# power_amplifier.net
KiCad netlist of a schematic drawn in Altium Designer
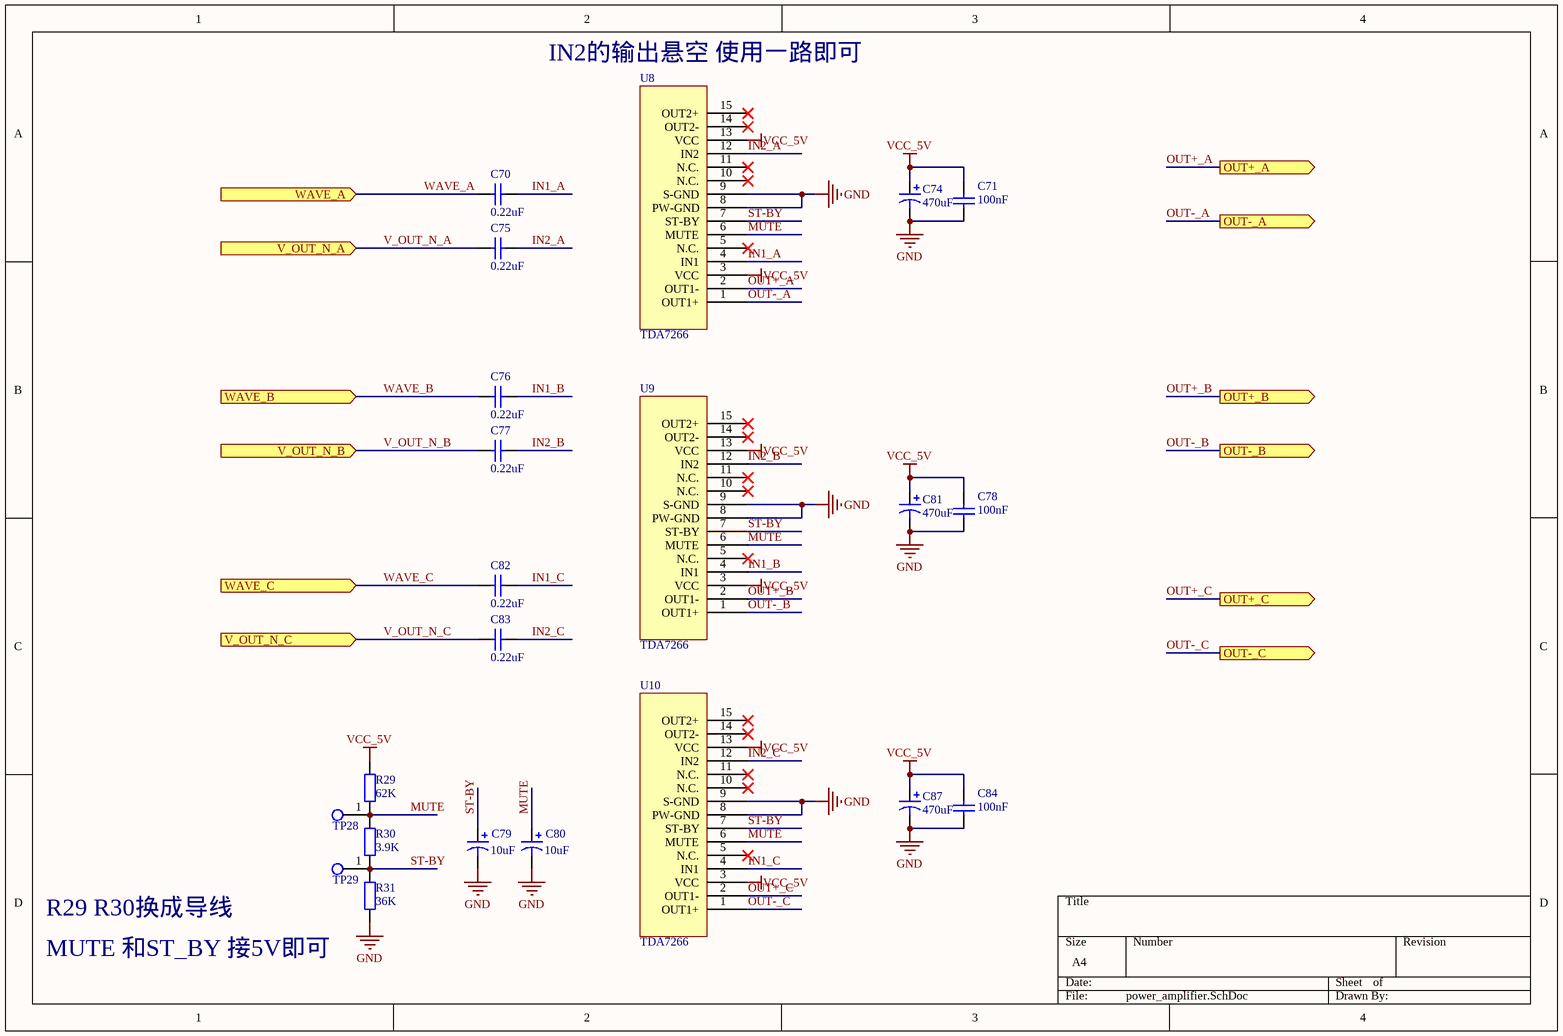
[diagram p0: power_amplifier.SchDoc]

(export (version "E")
  (design (tool "Eeschema 10.0.6"))
  (components
    (comp (ref "C70")
      (value "0.22uF")
      (footprint "0603")
      (fields
        (field (name "Comment") "Cap")
        (field (name "原理图绘制者") "刘永钦")
        (field (name "原理图提供者") "刘永钦")
        (field (name "原理图审核人1") "徐鹏飞")
        (field (name "封装0805绘制者") "刘永钦")
        (field (name "封装0805提供者") "刘永钦")
        (field (name "封装0805审核人1") "徐鹏飞")
        (field (name "原理图审核人2") "朱觉文")
        (field (name "封装0805审核人2") "朱觉文")
        (field (name "封装0603绘制者") "刘永钦")
        (field (name "封装0603提供者") "刘永钦")
        (field (name "封装0603审核人1") "朱觉文")
        (field (name "封装0603审核人2") "徐鹏飞")
      )
      (libsource (lib "自动化研究所集成库20170318") (part "Cap"))
    )
    (comp (ref "C71")
      (value "100nF")
      (footprint "0603")
      (fields
        (field (name "Comment") "Cap")
        (field (name "原理图绘制者") "刘永钦")
        (field (name "原理图提供者") "刘永钦")
        (field (name "原理图审核人1") "徐鹏飞")
        (field (name "封装0805绘制者") "刘永钦")
        (field (name "封装0805提供者") "刘永钦")
        (field (name "封装0805审核人1") "徐鹏飞")
        (field (name "原理图审核人2") "朱觉文")
        (field (name "封装0805审核人2") "朱觉文")
        (field (name "封装0603绘制者") "刘永钦")
        (field (name "封装0603提供者") "刘永钦")
        (field (name "封装0603审核人1") "朱觉文")
        (field (name "封装0603审核人2") "徐鹏飞")
      )
      (libsource (lib "自动化研究所集成库20170318") (part "Cap"))
    )
    (comp (ref "C74")
      (value "470uF")
      (footprint "cap贴片铝电解质470uF 16V")
      (fields
        (field (name "Comment") "Cap Poll")
        (field (name "原理图绘制者") "刘永钦")
        (field (name "原理图提供者") "刘永钦")
        (field (name "原理图审核人1") "徐鹏飞")
        (field (name "封装CAP 钽 7343 E绘制者") "刘永钦")
        (field (name "封装CAP 钽 7343 E提供者") "刘永钦")
        (field (name "封装CAP 钽 7343 E审核人1") "徐鹏飞")
        (field (name "封装CAP贴片铝电解质470UF 16V绘制者") "李泽")
        (field (name "封装CAP贴片铝电解质470UF 16V提供者") "刘永钦")
        (field (name "封装CAP贴片铝电解质470UF 16V审核人1") "徐鹏飞")
        (field (name "封装CAP 3528B绘制者") "陈汉诚")
        (field (name "封装CAP 3528B提供者") "刘永钦")
        (field (name "封装CAP 3528B审核人1") "徐鹏飞")
        (field (name "封装CAP直插 10UF 50V提供者") "刘永钦")
        (field (name "封装CAP直插 10UF 50V审核人1") "徐鹏飞")
        (field (name "封装CAP 3528B审核人2") "朱觉文")
        (field (name "封装CAP直插 10UF 50V审核人2") "朱觉文")
        (field (name "封装CAP贴片铝电解质470UF 16V审核人2") "朱觉文")
        (field (name "封装CAP 钽 7343 E审核人2") "朱觉文")
        (field (name "原理图审核人2") "朱觉文")
      )
      (libsource (lib "自动化研究所集成库20170318") (part "Cap Poll"))
    )
    (comp (ref "C75")
      (value "0.22uF")
      (footprint "0603")
      (fields
        (field (name "Comment") "Cap")
        (field (name "原理图绘制者") "刘永钦")
        (field (name "原理图提供者") "刘永钦")
        (field (name "原理图审核人1") "徐鹏飞")
        (field (name "封装0805绘制者") "刘永钦")
        (field (name "封装0805提供者") "刘永钦")
        (field (name "封装0805审核人1") "徐鹏飞")
        (field (name "原理图审核人2") "朱觉文")
        (field (name "封装0805审核人2") "朱觉文")
        (field (name "封装0603绘制者") "刘永钦")
        (field (name "封装0603提供者") "刘永钦")
        (field (name "封装0603审核人1") "朱觉文")
        (field (name "封装0603审核人2") "徐鹏飞")
      )
      (libsource (lib "自动化研究所集成库20170318") (part "Cap"))
    )
    (comp (ref "C76")
      (value "0.22uF")
      (footprint "0603")
      (fields
        (field (name "Comment") "Cap")
        (field (name "原理图绘制者") "刘永钦")
        (field (name "原理图提供者") "刘永钦")
        (field (name "原理图审核人1") "徐鹏飞")
        (field (name "封装0805绘制者") "刘永钦")
        (field (name "封装0805提供者") "刘永钦")
        (field (name "封装0805审核人1") "徐鹏飞")
        (field (name "原理图审核人2") "朱觉文")
        (field (name "封装0805审核人2") "朱觉文")
        (field (name "封装0603绘制者") "刘永钦")
        (field (name "封装0603提供者") "刘永钦")
        (field (name "封装0603审核人1") "朱觉文")
        (field (name "封装0603审核人2") "徐鹏飞")
      )
      (libsource (lib "自动化研究所集成库20170318") (part "Cap"))
    )
    (comp (ref "C77")
      (value "0.22uF")
      (footprint "0603")
      (fields
        (field (name "Comment") "Cap")
        (field (name "原理图绘制者") "刘永钦")
        (field (name "原理图提供者") "刘永钦")
        (field (name "原理图审核人1") "徐鹏飞")
        (field (name "封装0805绘制者") "刘永钦")
        (field (name "封装0805提供者") "刘永钦")
        (field (name "封装0805审核人1") "徐鹏飞")
        (field (name "原理图审核人2") "朱觉文")
        (field (name "封装0805审核人2") "朱觉文")
        (field (name "封装0603绘制者") "刘永钦")
        (field (name "封装0603提供者") "刘永钦")
        (field (name "封装0603审核人1") "朱觉文")
        (field (name "封装0603审核人2") "徐鹏飞")
      )
      (libsource (lib "自动化研究所集成库20170318") (part "Cap"))
    )
    (comp (ref "C78")
      (value "100nF")
      (footprint "0603")
      (fields
        (field (name "Comment") "Cap")
        (field (name "原理图绘制者") "刘永钦")
        (field (name "原理图提供者") "刘永钦")
        (field (name "原理图审核人1") "徐鹏飞")
        (field (name "封装0805绘制者") "刘永钦")
        (field (name "封装0805提供者") "刘永钦")
        (field (name "封装0805审核人1") "徐鹏飞")
        (field (name "原理图审核人2") "朱觉文")
        (field (name "封装0805审核人2") "朱觉文")
        (field (name "封装0603绘制者") "刘永钦")
        (field (name "封装0603提供者") "刘永钦")
        (field (name "封装0603审核人1") "朱觉文")
        (field (name "封装0603审核人2") "徐鹏飞")
      )
      (libsource (lib "自动化研究所集成库20170318") (part "Cap"))
    )
    (comp (ref "C79")
      (value "10uF")
      (footprint "Cap 3528B")
      (fields
        (field (name "Comment") "Cap Poll")
        (field (name "原理图绘制者") "刘永钦")
        (field (name "原理图提供者") "刘永钦")
        (field (name "原理图审核人1") "徐鹏飞")
        (field (name "封装CAP 钽 7343 E绘制者") "刘永钦")
        (field (name "封装CAP 钽 7343 E提供者") "刘永钦")
        (field (name "封装CAP 钽 7343 E审核人1") "徐鹏飞")
        (field (name "封装CAP贴片铝电解质470UF 16V绘制者") "李泽")
        (field (name "封装CAP贴片铝电解质470UF 16V提供者") "刘永钦")
        (field (name "封装CAP贴片铝电解质470UF 16V审核人1") "徐鹏飞")
        (field (name "封装CAP 3528B绘制者") "陈汉诚")
        (field (name "封装CAP 3528B提供者") "刘永钦")
        (field (name "封装CAP 3528B审核人1") "徐鹏飞")
        (field (name "封装CAP直插 10UF 50V提供者") "刘永钦")
        (field (name "封装CAP直插 10UF 50V审核人1") "徐鹏飞")
        (field (name "封装CAP 3528B审核人2") "朱觉文")
        (field (name "封装CAP直插 10UF 50V审核人2") "朱觉文")
        (field (name "封装CAP贴片铝电解质470UF 16V审核人2") "朱觉文")
        (field (name "封装CAP 钽 7343 E审核人2") "朱觉文")
        (field (name "原理图审核人2") "朱觉文")
      )
      (libsource (lib "自动化研究所集成库20170318") (part "Cap Poll"))
    )
    (comp (ref "C80")
      (value "10uF")
      (footprint "Cap 3528B")
      (fields
        (field (name "Comment") "Cap Poll")
        (field (name "原理图绘制者") "刘永钦")
        (field (name "原理图提供者") "刘永钦")
        (field (name "原理图审核人1") "徐鹏飞")
        (field (name "封装CAP 钽 7343 E绘制者") "刘永钦")
        (field (name "封装CAP 钽 7343 E提供者") "刘永钦")
        (field (name "封装CAP 钽 7343 E审核人1") "徐鹏飞")
        (field (name "封装CAP贴片铝电解质470UF 16V绘制者") "李泽")
        (field (name "封装CAP贴片铝电解质470UF 16V提供者") "刘永钦")
        (field (name "封装CAP贴片铝电解质470UF 16V审核人1") "徐鹏飞")
        (field (name "封装CAP 3528B绘制者") "陈汉诚")
        (field (name "封装CAP 3528B提供者") "刘永钦")
        (field (name "封装CAP 3528B审核人1") "徐鹏飞")
        (field (name "封装CAP直插 10UF 50V提供者") "刘永钦")
        (field (name "封装CAP直插 10UF 50V审核人1") "徐鹏飞")
        (field (name "封装CAP 3528B审核人2") "朱觉文")
        (field (name "封装CAP直插 10UF 50V审核人2") "朱觉文")
        (field (name "封装CAP贴片铝电解质470UF 16V审核人2") "朱觉文")
        (field (name "封装CAP 钽 7343 E审核人2") "朱觉文")
        (field (name "原理图审核人2") "朱觉文")
      )
      (libsource (lib "自动化研究所集成库20170318") (part "Cap Poll"))
    )
    (comp (ref "C81")
      (value "470uF")
      (footprint "cap贴片铝电解质470uF 16V")
      (fields
        (field (name "Comment") "Cap Poll")
        (field (name "原理图绘制者") "刘永钦")
        (field (name "原理图提供者") "刘永钦")
        (field (name "原理图审核人1") "徐鹏飞")
        (field (name "封装CAP 钽 7343 E绘制者") "刘永钦")
        (field (name "封装CAP 钽 7343 E提供者") "刘永钦")
        (field (name "封装CAP 钽 7343 E审核人1") "徐鹏飞")
        (field (name "封装CAP贴片铝电解质470UF 16V绘制者") "李泽")
        (field (name "封装CAP贴片铝电解质470UF 16V提供者") "刘永钦")
        (field (name "封装CAP贴片铝电解质470UF 16V审核人1") "徐鹏飞")
        (field (name "封装CAP 3528B绘制者") "陈汉诚")
        (field (name "封装CAP 3528B提供者") "刘永钦")
        (field (name "封装CAP 3528B审核人1") "徐鹏飞")
        (field (name "封装CAP直插 10UF 50V提供者") "刘永钦")
        (field (name "封装CAP直插 10UF 50V审核人1") "徐鹏飞")
        (field (name "封装CAP 3528B审核人2") "朱觉文")
        (field (name "封装CAP直插 10UF 50V审核人2") "朱觉文")
        (field (name "封装CAP贴片铝电解质470UF 16V审核人2") "朱觉文")
        (field (name "封装CAP 钽 7343 E审核人2") "朱觉文")
        (field (name "原理图审核人2") "朱觉文")
      )
      (libsource (lib "自动化研究所集成库20170318") (part "Cap Poll"))
    )
    (comp (ref "C82")
      (value "0.22uF")
      (footprint "0603")
      (fields
        (field (name "Comment") "Cap")
        (field (name "原理图绘制者") "刘永钦")
        (field (name "原理图提供者") "刘永钦")
        (field (name "原理图审核人1") "徐鹏飞")
        (field (name "封装0805绘制者") "刘永钦")
        (field (name "封装0805提供者") "刘永钦")
        (field (name "封装0805审核人1") "徐鹏飞")
        (field (name "原理图审核人2") "朱觉文")
        (field (name "封装0805审核人2") "朱觉文")
        (field (name "封装0603绘制者") "刘永钦")
        (field (name "封装0603提供者") "刘永钦")
        (field (name "封装0603审核人1") "朱觉文")
        (field (name "封装0603审核人2") "徐鹏飞")
      )
      (libsource (lib "自动化研究所集成库20170318") (part "Cap"))
    )
    (comp (ref "C83")
      (value "0.22uF")
      (footprint "0603")
      (fields
        (field (name "Comment") "Cap")
        (field (name "原理图绘制者") "刘永钦")
        (field (name "原理图提供者") "刘永钦")
        (field (name "原理图审核人1") "徐鹏飞")
        (field (name "封装0805绘制者") "刘永钦")
        (field (name "封装0805提供者") "刘永钦")
        (field (name "封装0805审核人1") "徐鹏飞")
        (field (name "原理图审核人2") "朱觉文")
        (field (name "封装0805审核人2") "朱觉文")
        (field (name "封装0603绘制者") "刘永钦")
        (field (name "封装0603提供者") "刘永钦")
        (field (name "封装0603审核人1") "朱觉文")
        (field (name "封装0603审核人2") "徐鹏飞")
      )
      (libsource (lib "自动化研究所集成库20170318") (part "Cap"))
    )
    (comp (ref "C84")
      (value "100nF")
      (footprint "0603")
      (fields
        (field (name "Comment") "Cap")
        (field (name "原理图绘制者") "刘永钦")
        (field (name "原理图提供者") "刘永钦")
        (field (name "原理图审核人1") "徐鹏飞")
        (field (name "封装0805绘制者") "刘永钦")
        (field (name "封装0805提供者") "刘永钦")
        (field (name "封装0805审核人1") "徐鹏飞")
        (field (name "原理图审核人2") "朱觉文")
        (field (name "封装0805审核人2") "朱觉文")
        (field (name "封装0603绘制者") "刘永钦")
        (field (name "封装0603提供者") "刘永钦")
        (field (name "封装0603审核人1") "朱觉文")
        (field (name "封装0603审核人2") "徐鹏飞")
      )
      (libsource (lib "自动化研究所集成库20170318") (part "Cap"))
    )
    (comp (ref "C87")
      (value "470uF")
      (footprint "cap贴片铝电解质470uF 16V")
      (fields
        (field (name "Comment") "Cap Poll")
        (field (name "原理图绘制者") "刘永钦")
        (field (name "原理图提供者") "刘永钦")
        (field (name "原理图审核人1") "徐鹏飞")
        (field (name "封装CAP 钽 7343 E绘制者") "刘永钦")
        (field (name "封装CAP 钽 7343 E提供者") "刘永钦")
        (field (name "封装CAP 钽 7343 E审核人1") "徐鹏飞")
        (field (name "封装CAP贴片铝电解质470UF 16V绘制者") "李泽")
        (field (name "封装CAP贴片铝电解质470UF 16V提供者") "刘永钦")
        (field (name "封装CAP贴片铝电解质470UF 16V审核人1") "徐鹏飞")
        (field (name "封装CAP 3528B绘制者") "陈汉诚")
        (field (name "封装CAP 3528B提供者") "刘永钦")
        (field (name "封装CAP 3528B审核人1") "徐鹏飞")
        (field (name "封装CAP直插 10UF 50V提供者") "刘永钦")
        (field (name "封装CAP直插 10UF 50V审核人1") "徐鹏飞")
        (field (name "封装CAP 3528B审核人2") "朱觉文")
        (field (name "封装CAP直插 10UF 50V审核人2") "朱觉文")
        (field (name "封装CAP贴片铝电解质470UF 16V审核人2") "朱觉文")
        (field (name "封装CAP 钽 7343 E审核人2") "朱觉文")
        (field (name "原理图审核人2") "朱觉文")
      )
      (libsource (lib "自动化研究所集成库20170318") (part "Cap Poll"))
    )
    (comp (ref "R29")
      (value "62K")
      (footprint "0603")
      (fields
        (field (name "Comment") "Res")
        (field (name "原理图绘制者") "刘永钦")
        (field (name "原理图提供者") "刘永钦")
        (field (name "原理图审核人1") "徐鹏飞")
        (field (name "封装0805绘制者") "刘永钦")
        (field (name "封装0805提供者") "刘永钦")
        (field (name "封装0805审核人1") "徐鹏飞")
        (field (name "原理图审核人2") "朱觉文")
        (field (name "封装0805审核人2") "朱觉文")
        (field (name "封装0603提供者") "刘永钦")
        (field (name "封装0603审核人2") "朱觉文")
        (field (name "封装0603审核人1") "徐鹏飞")
        (field (name "封装2512-RESC6332X06N审核人2") "朱觉文")
        (field (name "封装2512-RESC6332X06N提供者") "刘永钦")
        (field (name "封装2512-RESC6332X06N审核人1") "徐鹏飞")
        (field (name "封装0603绘制者") "刘永钦")
        (field (name "封装2512-RESC6332X06N绘制者") "刘永钦")
      )
      (libsource (lib "自动化研究所集成库20170318") (part "Res"))
    )
    (comp (ref "R30")
      (value "3.9K")
      (footprint "0603")
      (fields
        (field (name "Comment") "Res")
        (field (name "原理图绘制者") "刘永钦")
        (field (name "原理图提供者") "刘永钦")
        (field (name "原理图审核人1") "徐鹏飞")
        (field (name "封装0805绘制者") "刘永钦")
        (field (name "封装0805提供者") "刘永钦")
        (field (name "封装0805审核人1") "徐鹏飞")
        (field (name "原理图审核人2") "朱觉文")
        (field (name "封装0805审核人2") "朱觉文")
        (field (name "封装0603提供者") "刘永钦")
        (field (name "封装0603审核人2") "朱觉文")
        (field (name "封装0603审核人1") "徐鹏飞")
        (field (name "封装2512-RESC6332X06N审核人2") "朱觉文")
        (field (name "封装2512-RESC6332X06N提供者") "刘永钦")
        (field (name "封装2512-RESC6332X06N审核人1") "徐鹏飞")
        (field (name "封装0603绘制者") "刘永钦")
        (field (name "封装2512-RESC6332X06N绘制者") "刘永钦")
      )
      (libsource (lib "自动化研究所集成库20170318") (part "Res"))
    )
    (comp (ref "R31")
      (value "36K")
      (footprint "0603")
      (fields
        (field (name "Comment") "Res")
        (field (name "原理图绘制者") "刘永钦")
        (field (name "原理图提供者") "刘永钦")
        (field (name "原理图审核人1") "徐鹏飞")
        (field (name "封装0805绘制者") "刘永钦")
        (field (name "封装0805提供者") "刘永钦")
        (field (name "封装0805审核人1") "徐鹏飞")
        (field (name "原理图审核人2") "朱觉文")
        (field (name "封装0805审核人2") "朱觉文")
        (field (name "封装0603提供者") "刘永钦")
        (field (name "封装0603审核人2") "朱觉文")
        (field (name "封装0603审核人1") "徐鹏飞")
        (field (name "封装2512-RESC6332X06N审核人2") "朱觉文")
        (field (name "封装2512-RESC6332X06N提供者") "刘永钦")
        (field (name "封装2512-RESC6332X06N审核人1") "徐鹏飞")
        (field (name "封装0603绘制者") "刘永钦")
        (field (name "封装2512-RESC6332X06N绘制者") "刘永钦")
      )
      (libsource (lib "") (part "Res_1"))
    )
    (comp (ref "TP28") (value "testPoint") (footprint "TP_H") (libsource (lib "Spartan") (part "TP")))
    (comp (ref "TP29") (value "testPoint") (footprint "TP_H") (libsource (lib "Spartan") (part "TP")))
    (comp (ref "U8") (value "TDA7266") (footprint "TDA7266") (libsource (lib "Dugu") (part "TDA7266")))
    (comp (ref "U9") (value "TDA7266") (footprint "TDA7266") (libsource (lib "Dugu") (part "TDA7266")))
    (comp (ref "U10") (value "TDA7266") (footprint "TDA7266") (libsource (lib "Dugu") (part "TDA7266")))
  )
  (nets
    (net (code "1") (name "/IN1_A") (class "Default")
      (node (ref "C70") (pin "2") (pinfunction "2_2") (pintype "passive"))
      (node (ref "U8") (pin "4") (pinfunction "IN1_4") (pintype "passive"))
    )
    (net (code "2") (name "/IN1_B") (class "Default")
      (node (ref "C76") (pin "2") (pinfunction "2_2") (pintype "passive"))
      (node (ref "U9") (pin "4") (pinfunction "IN1_4") (pintype "passive"))
    )
    (net (code "3") (name "/IN1_C") (class "Default")
      (node (ref "C82") (pin "2") (pinfunction "2_2") (pintype "passive"))
      (node (ref "U10") (pin "4") (pinfunction "IN1_4") (pintype "passive"))
    )
    (net (code "4") (name "/IN2_A") (class "Default")
      (node (ref "C75") (pin "2") (pinfunction "2_2") (pintype "passive"))
      (node (ref "U8") (pin "12") (pinfunction "IN2_12") (pintype "passive"))
    )
    (net (code "5") (name "/IN2_B") (class "Default")
      (node (ref "C77") (pin "2") (pinfunction "2_2") (pintype "passive"))
      (node (ref "U9") (pin "12") (pinfunction "IN2_12") (pintype "passive"))
    )
    (net (code "6") (name "/IN2_C") (class "Default")
      (node (ref "C83") (pin "2") (pinfunction "2_2") (pintype "passive"))
      (node (ref "U10") (pin "12") (pinfunction "IN2_12") (pintype "passive"))
    )
    (net (code "7") (name "/MUTE") (class "Default")
      (node (ref "C80") (pin "1") (pinfunction "1_1") (pintype "passive"))
      (node (ref "R29") (pin "2") (pinfunction "2_2") (pintype "passive"))
      (node (ref "R30") (pin "1") (pinfunction "1_1") (pintype "passive"))
      (node (ref "TP28") (pin "1") (pinfunction "1_1") (pintype "passive"))
      (node (ref "U10") (pin "6") (pinfunction "MUTE_6") (pintype "passive"))
      (node (ref "U8") (pin "6") (pinfunction "MUTE_6") (pintype "passive"))
      (node (ref "U9") (pin "6") (pinfunction "MUTE_6") (pintype "passive"))
    )
    (net (code "8") (name "/OUT+_A") (class "Default")
      (node (ref "U8") (pin "2") (pinfunction "OUT1-_2") (pintype "passive"))
    )
    (net (code "9") (name "/OUT+_B") (class "Default")
      (node (ref "U9") (pin "2") (pinfunction "OUT1-_2") (pintype "passive"))
    )
    (net (code "10") (name "/OUT+_C") (class "Default")
      (node (ref "U10") (pin "2") (pinfunction "OUT1-_2") (pintype "passive"))
    )
    (net (code "11") (name "/OUT-_A") (class "Default")
      (node (ref "U8") (pin "1") (pinfunction "OUT1+_1") (pintype "passive"))
    )
    (net (code "12") (name "/OUT-_B") (class "Default")
      (node (ref "U9") (pin "1") (pinfunction "OUT1+_1") (pintype "passive"))
    )
    (net (code "13") (name "/OUT-_C") (class "Default")
      (node (ref "U10") (pin "1") (pinfunction "OUT1+_1") (pintype "passive"))
    )
    (net (code "14") (name "/ST-BY") (class "Default")
      (node (ref "C79") (pin "1") (pinfunction "1_1") (pintype "passive"))
      (node (ref "R30") (pin "2") (pinfunction "2_2") (pintype "passive"))
      (node (ref "R31") (pin "2") (pinfunction "2_2") (pintype "passive"))
      (node (ref "TP29") (pin "1") (pinfunction "1_1") (pintype "passive"))
      (node (ref "U10") (pin "7") (pinfunction "ST-BY_7") (pintype "passive"))
      (node (ref "U8") (pin "7") (pinfunction "ST-BY_7") (pintype "passive"))
      (node (ref "U9") (pin "7") (pinfunction "ST-BY_7") (pintype "passive"))
    )
    (net (code "15") (name "/V_OUT_N_A") (class "Default")
      (node (ref "C75") (pin "1") (pinfunction "1_1") (pintype "passive"))
    )
    (net (code "16") (name "/V_OUT_N_B") (class "Default")
      (node (ref "C77") (pin "1") (pinfunction "1_1") (pintype "passive"))
    )
    (net (code "17") (name "/V_OUT_N_C") (class "Default")
      (node (ref "C83") (pin "1") (pinfunction "1_1") (pintype "passive"))
    )
    (net (code "18") (name "/WAVE_A") (class "Default")
      (node (ref "C70") (pin "1") (pinfunction "1_1") (pintype "passive"))
    )
    (net (code "19") (name "/WAVE_B") (class "Default")
      (node (ref "C76") (pin "1") (pinfunction "1_1") (pintype "passive"))
    )
    (net (code "20") (name "/WAVE_C") (class "Default")
      (node (ref "C82") (pin "1") (pinfunction "1_1") (pintype "passive"))
    )
    (net (code "21") (name "GND") (class "Default")
      (node (ref "C71") (pin "1") (pinfunction "1_1") (pintype "passive"))
      (node (ref "C74") (pin "2") (pinfunction "2_2") (pintype "passive"))
      (node (ref "C78") (pin "1") (pinfunction "1_1") (pintype "passive"))
      (node (ref "C79") (pin "2") (pinfunction "2_2") (pintype "passive"))
      (node (ref "C80") (pin "2") (pinfunction "2_2") (pintype "passive"))
      (node (ref "C81") (pin "2") (pinfunction "2_2") (pintype "passive"))
      (node (ref "C84") (pin "1") (pinfunction "1_1") (pintype "passive"))
      (node (ref "C87") (pin "2") (pinfunction "2_2") (pintype "passive"))
      (node (ref "R31") (pin "1") (pinfunction "1_1") (pintype "passive"))
      (node (ref "U10") (pin "8") (pinfunction "PW-GND_8") (pintype "passive"))
      (node (ref "U10") (pin "9") (pinfunction "S-GND_9") (pintype "passive"))
      (node (ref "U8") (pin "8") (pinfunction "PW-GND_8") (pintype "passive"))
      (node (ref "U8") (pin "9") (pinfunction "S-GND_9") (pintype "passive"))
      (node (ref "U9") (pin "8") (pinfunction "PW-GND_8") (pintype "passive"))
      (node (ref "U9") (pin "9") (pinfunction "S-GND_9") (pintype "passive"))
    )
    (net (code "22") (name "VCC_5V") (class "Default")
      (node (ref "C71") (pin "2") (pinfunction "2_2") (pintype "passive"))
      (node (ref "C74") (pin "1") (pinfunction "1_1") (pintype "passive"))
      (node (ref "C78") (pin "2") (pinfunction "2_2") (pintype "passive"))
      (node (ref "C81") (pin "1") (pinfunction "1_1") (pintype "passive"))
      (node (ref "C84") (pin "2") (pinfunction "2_2") (pintype "passive"))
      (node (ref "C87") (pin "1") (pinfunction "1_1") (pintype "passive"))
      (node (ref "R29") (pin "1") (pinfunction "1_1") (pintype "passive"))
      (node (ref "U10") (pin "13") (pinfunction "VCC_13") (pintype "passive"))
      (node (ref "U10") (pin "3") (pinfunction "VCC_3") (pintype "passive"))
      (node (ref "U8") (pin "13") (pinfunction "VCC_13") (pintype "passive"))
      (node (ref "U8") (pin "3") (pinfunction "VCC_3") (pintype "passive"))
      (node (ref "U9") (pin "13") (pinfunction "VCC_13") (pintype "passive"))
      (node (ref "U9") (pin "3") (pinfunction "VCC_3") (pintype "passive"))
    )
    (net (code "23") (name "unconnected-(U8-N.C.-Pad5)") (class "Default")
      (node (ref "U8") (pin "5") (pinfunction "N.C._5") (pintype "passive+no_connect"))
    )
    (net (code "24") (name "unconnected-(U8-N.C.-Pad10)") (class "Default")
      (node (ref "U8") (pin "10") (pinfunction "N.C._10") (pintype "passive+no_connect"))
    )
    (net (code "25") (name "unconnected-(U8-N.C.-Pad11)") (class "Default")
      (node (ref "U8") (pin "11") (pinfunction "N.C._11") (pintype "passive+no_connect"))
    )
    (net (code "26") (name "unconnected-(U8-OUT2+-Pad15)") (class "Default")
      (node (ref "U8") (pin "15") (pinfunction "OUT2+_15") (pintype "passive+no_connect"))
    )
    (net (code "27") (name "unconnected-(U8-OUT2--Pad14)") (class "Default")
      (node (ref "U8") (pin "14") (pinfunction "OUT2-_14") (pintype "passive+no_connect"))
    )
    (net (code "28") (name "unconnected-(U9-N.C.-Pad5)") (class "Default")
      (node (ref "U9") (pin "5") (pinfunction "N.C._5") (pintype "passive+no_connect"))
    )
    (net (code "29") (name "unconnected-(U9-N.C.-Pad10)") (class "Default")
      (node (ref "U9") (pin "10") (pinfunction "N.C._10") (pintype "passive+no_connect"))
    )
    (net (code "30") (name "unconnected-(U9-N.C.-Pad11)") (class "Default")
      (node (ref "U9") (pin "11") (pinfunction "N.C._11") (pintype "passive+no_connect"))
    )
    (net (code "31") (name "unconnected-(U9-OUT2+-Pad15)") (class "Default")
      (node (ref "U9") (pin "15") (pinfunction "OUT2+_15") (pintype "passive+no_connect"))
    )
    (net (code "32") (name "unconnected-(U9-OUT2--Pad14)") (class "Default")
      (node (ref "U9") (pin "14") (pinfunction "OUT2-_14") (pintype "passive+no_connect"))
    )
    (net (code "33") (name "unconnected-(U10-N.C.-Pad5)") (class "Default")
      (node (ref "U10") (pin "5") (pinfunction "N.C._5") (pintype "passive+no_connect"))
    )
    (net (code "34") (name "unconnected-(U10-N.C.-Pad10)") (class "Default")
      (node (ref "U10") (pin "10") (pinfunction "N.C._10") (pintype "passive+no_connect"))
    )
    (net (code "35") (name "unconnected-(U10-N.C.-Pad11)") (class "Default")
      (node (ref "U10") (pin "11") (pinfunction "N.C._11") (pintype "passive+no_connect"))
    )
    (net (code "36") (name "unconnected-(U10-OUT2+-Pad15)") (class "Default")
      (node (ref "U10") (pin "15") (pinfunction "OUT2+_15") (pintype "passive+no_connect"))
    )
    (net (code "37") (name "unconnected-(U10-OUT2--Pad14)") (class "Default")
      (node (ref "U10") (pin "14") (pinfunction "OUT2-_14") (pintype "passive+no_connect"))
    )
  )
)
